# Fri3d_2024_CVR_00.net
KiCad netlist of a schematic drawn in Altium Designer
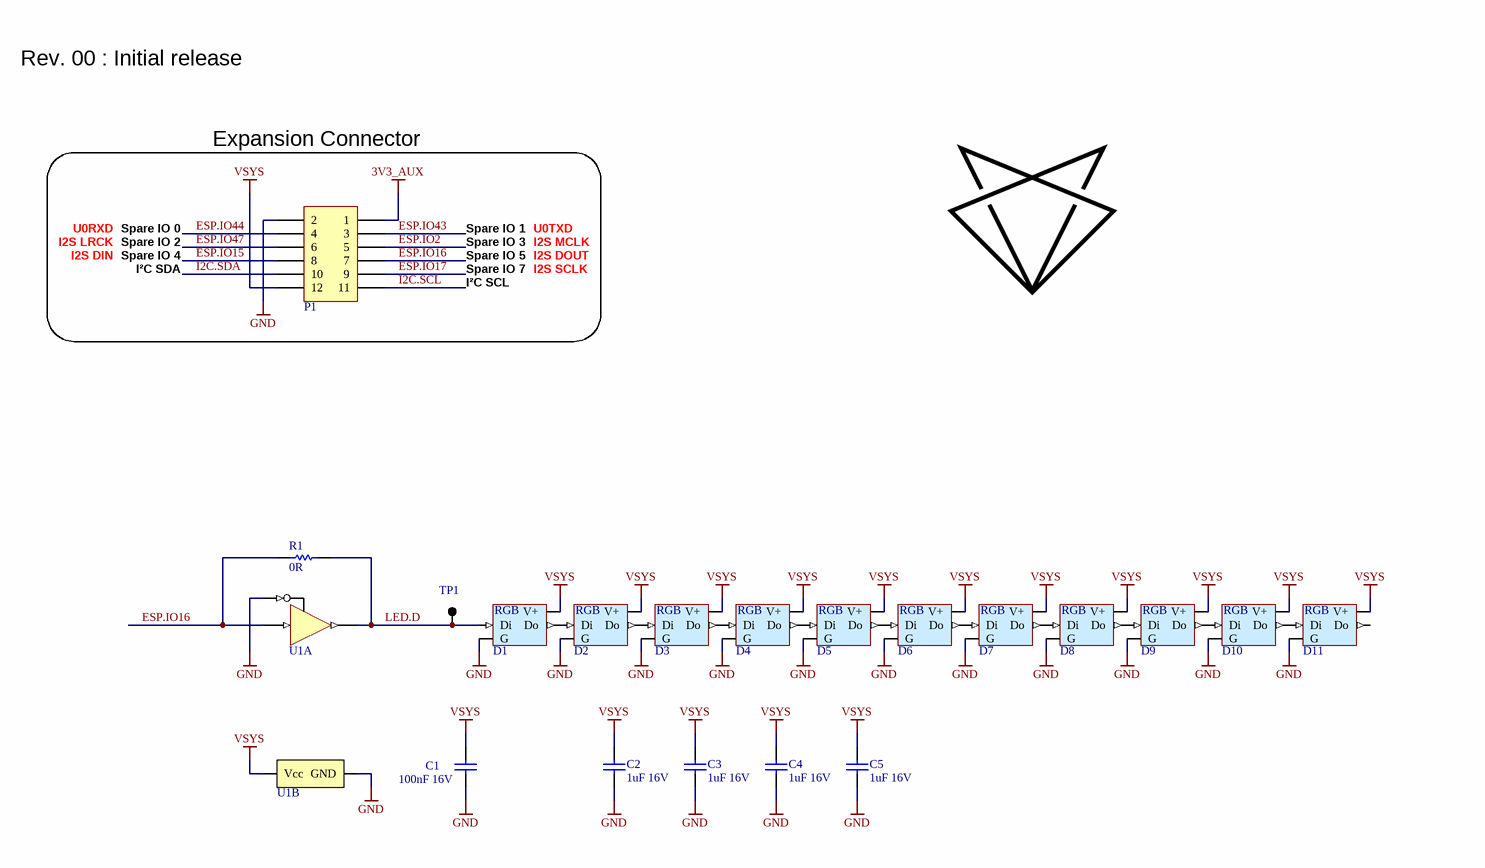
[diagram p0: Fri3d_2024_CVR_00.SchDoc]

(export (version "E")
  (design (tool "Eeschema 10.0.6"))
  (components
    (comp (ref "C1")
      (value "100nF 16V")
      (footprint "C0603_N")
      (description "Capacitor Ceramic")
      (libsource (lib "Phyx_Components") (part "CAP_CERAMIC"))
    )
    (comp (ref "C2")
      (value "1uF 16V")
      (footprint "C0603_N")
      (description "Capacitor Ceramic")
      (fields (field (name "Comment") "CAP_CERAMIC"))
      (libsource (lib "Phyx_Components") (part "CAP_CERAMIC"))
    )
    (comp (ref "C3")
      (value "1uF 16V")
      (footprint "C0603_N")
      (description "Capacitor Ceramic")
      (fields (field (name "Comment") "CAP_CERAMIC"))
      (libsource (lib "Phyx_Components") (part "CAP_CERAMIC"))
    )
    (comp (ref "C4")
      (value "1uF 16V")
      (footprint "C0603_N")
      (description "Capacitor Ceramic")
      (fields (field (name "Comment") "CAP_CERAMIC"))
      (libsource (lib "Phyx_Components") (part "CAP_CERAMIC"))
    )
    (comp (ref "C5")
      (value "1uF 16V")
      (footprint "C0603_N")
      (description "Capacitor Ceramic")
      (fields (field (name "Comment") "CAP_CERAMIC"))
      (libsource (lib "Phyx_Components") (part "CAP_CERAMIC"))
    )
    (comp (ref "D1")
      (value "WS2812 based digital RGB LED 4020 White package Side emitting")
      (footprint "LED_4020_WS2812B_WHITE")
      (description "=Description")
      (libsource (lib "Phyx_Components") (part "LED_RGB_WS2812B_4020"))
    )
    (comp (ref "D2")
      (value "WS2812 based digital RGB LED 4020 White package Side emitting")
      (footprint "LED_4020_WS2812B_WHITE")
      (description "=Description")
      (libsource (lib "Phyx_Components") (part "LED_RGB_WS2812B_4020"))
    )
    (comp (ref "D3")
      (value "WS2812 based digital RGB LED 4020 White package Side emitting")
      (footprint "LED_4020_WS2812B_WHITE")
      (description "=Description")
      (libsource (lib "Phyx_Components") (part "LED_RGB_WS2812B_4020"))
    )
    (comp (ref "D4")
      (value "WS2812 based digital RGB LED 4020 White package Side emitting")
      (footprint "LED_4020_WS2812B_WHITE")
      (description "=Description")
      (libsource (lib "Phyx_Components") (part "LED_RGB_WS2812B_4020"))
    )
    (comp (ref "D5")
      (value "WS2812 based digital RGB LED 4020 White package Side emitting")
      (footprint "LED_4020_WS2812B_WHITE")
      (description "=Description")
      (libsource (lib "Phyx_Components") (part "LED_RGB_WS2812B_4020"))
    )
    (comp (ref "D6")
      (value "WS2812 based digital RGB LED 4020 White package Side emitting")
      (footprint "LED_4020_WS2812B_WHITE")
      (description "=Description")
      (libsource (lib "Phyx_Components") (part "LED_RGB_WS2812B_4020"))
    )
    (comp (ref "D7")
      (value "WS2812 based digital RGB LED 4020 White package Side emitting")
      (footprint "LED_4020_WS2812B_WHITE")
      (description "=Description")
      (libsource (lib "Phyx_Components") (part "LED_RGB_WS2812B_4020"))
    )
    (comp (ref "D8")
      (value "WS2812 based digital RGB LED 4020 White package Side emitting")
      (footprint "LED_4020_WS2812B_WHITE")
      (description "=Description")
      (libsource (lib "Phyx_Components") (part "LED_RGB_WS2812B_4020"))
    )
    (comp (ref "D9")
      (value "WS2812 based digital RGB LED 4020 White package Side emitting")
      (footprint "LED_4020_WS2812B_WHITE")
      (description "=Description")
      (libsource (lib "Phyx_Components") (part "LED_RGB_WS2812B_4020"))
    )
    (comp (ref "D10")
      (value "WS2812 based digital RGB LED 4020 White package Side emitting")
      (footprint "LED_4020_WS2812B_WHITE")
      (description "=Description")
      (libsource (lib "Phyx_Components") (part "LED_RGB_WS2812B_4020"))
    )
    (comp (ref "D11")
      (value "WS2812 based digital RGB LED 4020 White package Side emitting")
      (footprint "LED_4020_WS2812B_WHITE")
      (description "=Description")
      (libsource (lib "Phyx_Components") (part "LED_RGB_WS2812B_4020"))
    )
    (comp (ref "P1")
      (value "Header 6X2")
      (footprint "HDR2X6")
      (libsource (lib "Phyx_Components") (part "Header 6X2"))
    )
    (comp (ref "R1")
      (value "0R")
      (footprint "R0402")
      (description "RES # 0R 0402")
      (fields (field (name "Comment") "RESISTOR"))
      (libsource (lib "Phyx_Components") (part "RESISTOR"))
    )
    (comp (ref "TP1")
      (value "TEST_PAD")
      (footprint "TP_2x3mm")
      (libsource (lib "Phyx_Components") (part "TEST_PAD"))
    )
    (comp (ref "U1")
      (value "SN74AHCT1G125DCKR  Buffer, Tri-State, 4.5V to 5.5V")
      (footprint "TI_DCK_R-PDSO-G5")
      (description "=Description")
      (libsource (lib "Phyx_Components") (part "SN74AHCT1G125"))
    )
  )
  (nets
    (net (code "2") (name "/ESP.IO2") (class "Default")
      (node (ref "P1") (pin "5") (pinfunction "5_5") (pintype "passive"))
    )
    (net (code "3") (name "/ESP.IO15") (class "Default")
      (node (ref "P1") (pin "8") (pinfunction "8_8") (pintype "passive"))
    )
    (net (code "4") (name "/ESP.IO16") (class "Default")
      (node (ref "P1") (pin "7") (pinfunction "7_7") (pintype "passive"))
      (node (ref "R1") (pin "2") (pinfunction "2_2") (pintype "passive"))
      (node (ref "U1") (pin "2") (pinfunction "A_2") (pintype "input"))
    )
    (net (code "5") (name "/ESP.IO17") (class "Default")
      (node (ref "P1") (pin "9") (pinfunction "9_9") (pintype "passive"))
    )
    (net (code "6") (name "/ESP.IO43") (class "Default")
      (node (ref "P1") (pin "3") (pinfunction "3_3") (pintype "passive"))
    )
    (net (code "7") (name "/ESP.IO44") (class "Default")
      (node (ref "P1") (pin "4") (pinfunction "4_4") (pintype "passive"))
    )
    (net (code "8") (name "/ESP.IO47") (class "Default")
      (node (ref "P1") (pin "6") (pinfunction "6_6") (pintype "passive"))
    )
    (net (code "9") (name "/I2C.SCL") (class "Default")
      (node (ref "P1") (pin "11") (pinfunction "11_11") (pintype "passive"))
    )
    (net (code "10") (name "/I2C.SDA") (class "Default")
      (node (ref "P1") (pin "10") (pinfunction "10_10") (pintype "passive"))
    )
    (net (code "11") (name "/LED.D") (class "Default")
      (node (ref "D1") (pin "1") (pinfunction "Di_1") (pintype "input"))
      (node (ref "R1") (pin "1") (pinfunction "1_1") (pintype "passive"))
      (node (ref "TP1") (pin "1") (pinfunction "1_1") (pintype "passive"))
      (node (ref "U1") (pin "4") (pinfunction "Y_4") (pintype "output"))
    )
    (net (code "12") (name "3V3_AUX") (class "Default")
      (node (ref "P1") (pin "1") (pinfunction "1_1") (pintype "passive"))
    )
    (net (code "13") (name "GND") (class "Default")
      (node (ref "C1") (pin "2") (pinfunction "2_2") (pintype "passive"))
      (node (ref "C2") (pin "2") (pinfunction "2_2") (pintype "passive"))
      (node (ref "C3") (pin "2") (pinfunction "2_2") (pintype "passive"))
      (node (ref "C4") (pin "2") (pinfunction "2_2") (pintype "passive"))
      (node (ref "C5") (pin "2") (pinfunction "2_2") (pintype "passive"))
      (node (ref "D1") (pin "4") (pinfunction "G_4") (pintype "power_in"))
      (node (ref "D10") (pin "4") (pinfunction "G_4") (pintype "power_in"))
      (node (ref "D11") (pin "4") (pinfunction "G_4") (pintype "power_in"))
      (node (ref "D2") (pin "4") (pinfunction "G_4") (pintype "power_in"))
      (node (ref "D3") (pin "4") (pinfunction "G_4") (pintype "power_in"))
      (node (ref "D4") (pin "4") (pinfunction "G_4") (pintype "power_in"))
      (node (ref "D5") (pin "4") (pinfunction "G_4") (pintype "power_in"))
      (node (ref "D6") (pin "4") (pinfunction "G_4") (pintype "power_in"))
      (node (ref "D7") (pin "4") (pinfunction "G_4") (pintype "power_in"))
      (node (ref "D8") (pin "4") (pinfunction "G_4") (pintype "power_in"))
      (node (ref "D9") (pin "4") (pinfunction "G_4") (pintype "power_in"))
      (node (ref "P1") (pin "2") (pinfunction "2_2") (pintype "passive"))
      (node (ref "U1") (pin "1") (pinfunction "~{OE}_1") (pintype "input"))
      (node (ref "U1") (pin "3") (pinfunction "GND_3") (pintype "power_in"))
    )
    (net (code "14") (name "Net-(D1-Do)") (class "Default")
      (node (ref "D1") (pin "3") (pinfunction "Do_3") (pintype "output"))
      (node (ref "D2") (pin "1") (pinfunction "Di_1") (pintype "input"))
    )
    (net (code "15") (name "Net-(D2-Do)") (class "Default")
      (node (ref "D2") (pin "3") (pinfunction "Do_3") (pintype "output"))
      (node (ref "D3") (pin "1") (pinfunction "Di_1") (pintype "input"))
    )
    (net (code "16") (name "Net-(D3-Do)") (class "Default")
      (node (ref "D3") (pin "3") (pinfunction "Do_3") (pintype "output"))
      (node (ref "D4") (pin "1") (pinfunction "Di_1") (pintype "input"))
    )
    (net (code "17") (name "Net-(D4-Do)") (class "Default")
      (node (ref "D4") (pin "3") (pinfunction "Do_3") (pintype "output"))
      (node (ref "D5") (pin "1") (pinfunction "Di_1") (pintype "input"))
    )
    (net (code "18") (name "Net-(D5-Do)") (class "Default")
      (node (ref "D5") (pin "3") (pinfunction "Do_3") (pintype "output"))
      (node (ref "D6") (pin "1") (pinfunction "Di_1") (pintype "input"))
    )
    (net (code "19") (name "Net-(D6-Do)") (class "Default")
      (node (ref "D6") (pin "3") (pinfunction "Do_3") (pintype "output"))
      (node (ref "D7") (pin "1") (pinfunction "Di_1") (pintype "input"))
    )
    (net (code "20") (name "Net-(D7-Do)") (class "Default")
      (node (ref "D7") (pin "3") (pinfunction "Do_3") (pintype "output"))
      (node (ref "D8") (pin "1") (pinfunction "Di_1") (pintype "input"))
    )
    (net (code "21") (name "Net-(D8-Do)") (class "Default")
      (node (ref "D8") (pin "3") (pinfunction "Do_3") (pintype "output"))
      (node (ref "D9") (pin "1") (pinfunction "Di_1") (pintype "input"))
    )
    (net (code "22") (name "Net-(D10-Di)") (class "Default")
      (node (ref "D10") (pin "1") (pinfunction "Di_1") (pintype "input"))
      (node (ref "D9") (pin "3") (pinfunction "Do_3") (pintype "output"))
    )
    (net (code "23") (name "Net-(D10-Do)") (class "Default")
      (node (ref "D10") (pin "3") (pinfunction "Do_3") (pintype "output"))
      (node (ref "D11") (pin "1") (pinfunction "Di_1") (pintype "input"))
    )
    (net (code "24") (name "VSYS") (class "Default")
      (node (ref "C1") (pin "1") (pinfunction "1_1") (pintype "passive"))
      (node (ref "C2") (pin "1") (pinfunction "1_1") (pintype "passive"))
      (node (ref "C3") (pin "1") (pinfunction "1_1") (pintype "passive"))
      (node (ref "C4") (pin "1") (pinfunction "1_1") (pintype "passive"))
      (node (ref "C5") (pin "1") (pinfunction "1_1") (pintype "passive"))
      (node (ref "D1") (pin "2") (pinfunction "V+_2") (pintype "power_in"))
      (node (ref "D10") (pin "2") (pinfunction "V+_2") (pintype "power_in"))
      (node (ref "D11") (pin "2") (pinfunction "V+_2") (pintype "power_in"))
      (node (ref "D2") (pin "2") (pinfunction "V+_2") (pintype "power_in"))
      (node (ref "D3") (pin "2") (pinfunction "V+_2") (pintype "power_in"))
      (node (ref "D4") (pin "2") (pinfunction "V+_2") (pintype "power_in"))
      (node (ref "D5") (pin "2") (pinfunction "V+_2") (pintype "power_in"))
      (node (ref "D6") (pin "2") (pinfunction "V+_2") (pintype "power_in"))
      (node (ref "D7") (pin "2") (pinfunction "V+_2") (pintype "power_in"))
      (node (ref "D8") (pin "2") (pinfunction "V+_2") (pintype "power_in"))
      (node (ref "D9") (pin "2") (pinfunction "V+_2") (pintype "power_in"))
      (node (ref "P1") (pin "12") (pinfunction "12_12") (pintype "passive"))
      (node (ref "U1") (pin "5") (pinfunction "Vcc_5") (pintype "power_in"))
    )
    (net (code "25") (name "unconnected-(D11-Do-Pad3)") (class "Default")
      (node (ref "D11") (pin "3") (pinfunction "Do_3") (pintype "output"))
    )
  )
)
